# PDM_2021.net
KiCad netlist of a schematic drawn in EAGLE
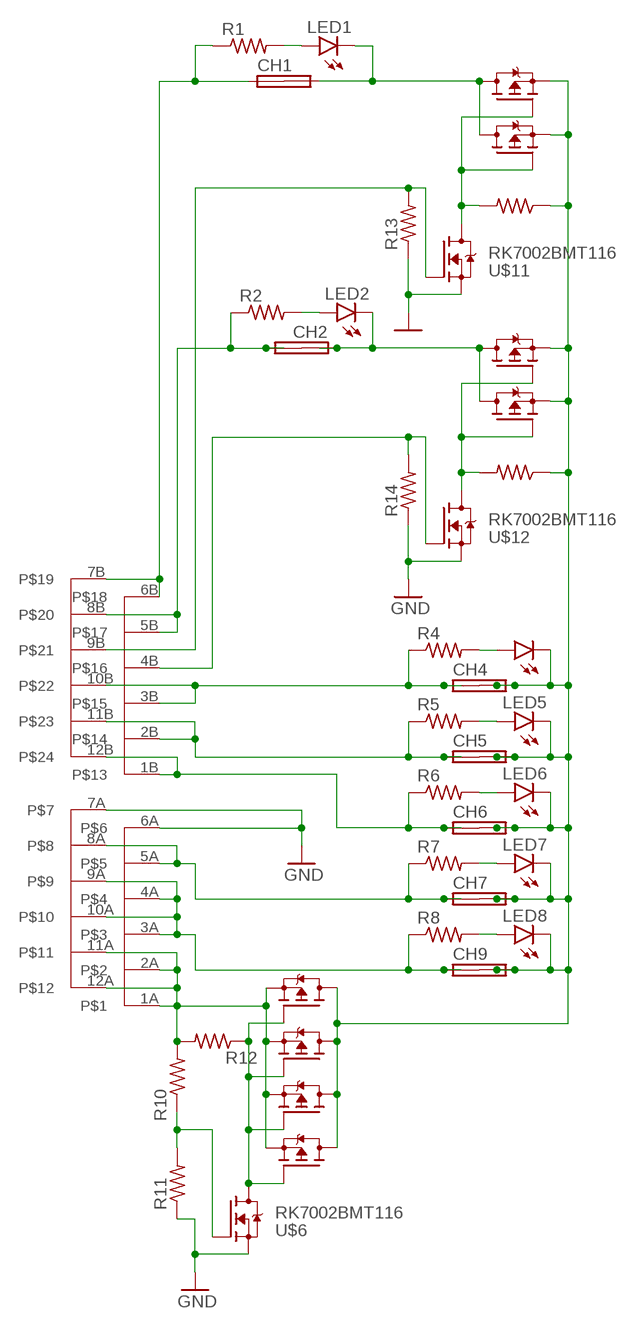
[diagram p0: schematic, sheet 1]

(export (version "E")
  (design (tool "Eeschema 10.0.6"))
  (components
    (comp (ref "CH1")
      (value "3568FUSEHOLDER")
      (footprint "eagle-import:3568")
      (libsource (lib "eagle-import") (part "3568FUSEHOLDER"))
    )
    (comp (ref "CH2")
      (value "3568FUSEHOLDER")
      (footprint "eagle-import:3568")
      (libsource (lib "eagle-import") (part "3568FUSEHOLDER"))
    )
    (comp (ref "CH4")
      (value "3568FUSEHOLDER")
      (footprint "eagle-import:3568")
      (libsource (lib "eagle-import") (part "3568FUSEHOLDER"))
    )
    (comp (ref "CH5")
      (value "3568FUSEHOLDER")
      (footprint "eagle-import:3568")
      (libsource (lib "eagle-import") (part "3568FUSEHOLDER"))
    )
    (comp (ref "CH6")
      (value "3568FUSEHOLDER")
      (footprint "eagle-import:3568")
      (libsource (lib "eagle-import") (part "3568FUSEHOLDER"))
    )
    (comp (ref "CH7")
      (value "3568FUSEHOLDER")
      (footprint "eagle-import:3568")
      (libsource (lib "eagle-import") (part "3568FUSEHOLDER"))
    )
    (comp (ref "CH9")
      (value "3568FUSEHOLDER")
      (footprint "eagle-import:3568")
      (libsource (lib "eagle-import") (part "3568FUSEHOLDER"))
    )
    (comp (ref "LED1")
      (value "LEDCHIP-LED0805")
      (footprint "eagle-import:CHIP-LED0805")
      (libsource (lib "eagle-import") (part "LEDCHIP-LED0805"))
    )
    (comp (ref "LED2")
      (value "LEDCHIP-LED0805")
      (footprint "eagle-import:CHIP-LED0805")
      (libsource (lib "eagle-import") (part "LEDCHIP-LED0805"))
    )
    (comp (ref "LED4")
      (value "LEDCHIP-LED0805")
      (footprint "eagle-import:CHIP-LED0805")
      (libsource (lib "eagle-import") (part "LEDCHIP-LED0805"))
    )
    (comp (ref "LED5")
      (value "LEDCHIP-LED0805")
      (footprint "eagle-import:CHIP-LED0805")
      (libsource (lib "eagle-import") (part "LEDCHIP-LED0805"))
    )
    (comp (ref "LED6")
      (value "LEDCHIP-LED0805")
      (footprint "eagle-import:CHIP-LED0805")
      (libsource (lib "eagle-import") (part "LEDCHIP-LED0805"))
    )
    (comp (ref "LED7")
      (value "LEDCHIP-LED0805")
      (footprint "eagle-import:CHIP-LED0805")
      (libsource (lib "eagle-import") (part "LEDCHIP-LED0805"))
    )
    (comp (ref "LED8")
      (value "LEDCHIP-LED0805")
      (footprint "eagle-import:CHIP-LED0805")
      (libsource (lib "eagle-import") (part "LEDCHIP-LED0805"))
    )
    (comp (ref "R1")
      (value "R-US_R0805")
      (footprint "eagle-import:R0805")
      (libsource (lib "eagle-import") (part "R-US_R0805"))
    )
    (comp (ref "R2")
      (value "R-US_R0805")
      (footprint "eagle-import:R0805")
      (libsource (lib "eagle-import") (part "R-US_R0805"))
    )
    (comp (ref "R4")
      (value "R-US_R0805")
      (footprint "eagle-import:R0805")
      (libsource (lib "eagle-import") (part "R-US_R0805"))
    )
    (comp (ref "R5")
      (value "R-US_R0805")
      (footprint "eagle-import:R0805")
      (libsource (lib "eagle-import") (part "R-US_R0805"))
    )
    (comp (ref "R6")
      (value "R-US_R0805")
      (footprint "eagle-import:R0805")
      (libsource (lib "eagle-import") (part "R-US_R0805"))
    )
    (comp (ref "R7")
      (value "R-US_R0805")
      (footprint "eagle-import:R0805")
      (libsource (lib "eagle-import") (part "R-US_R0805"))
    )
    (comp (ref "R8")
      (value "R-US_R0805")
      (footprint "eagle-import:R0805")
      (libsource (lib "eagle-import") (part "R-US_R0805"))
    )
    (comp (ref "R10")
      (value "R-US_R0805")
      (footprint "eagle-import:R0805")
      (libsource (lib "eagle-import") (part "R-US_R0805"))
    )
    (comp (ref "R11")
      (value "R-US_R0805")
      (footprint "eagle-import:R0805")
      (libsource (lib "eagle-import") (part "R-US_R0805"))
    )
    (comp (ref "R12")
      (value "R-US_R0805")
      (footprint "eagle-import:R0805")
      (libsource (lib "eagle-import") (part "R-US_R0805"))
    )
    (comp (ref "R13")
      (value "R-US_R0805")
      (footprint "eagle-import:R0805")
      (libsource (lib "eagle-import") (part "R-US_R0805"))
    )
    (comp (ref "R14")
      (value "R-US_R0805")
      (footprint "eagle-import:R0805")
      (libsource (lib "eagle-import") (part "R-US_R0805"))
    )
    (comp (ref "R15")
      (value "R-US_R0805")
      (footprint "eagle-import:R0805")
      (libsource (lib "eagle-import") (part "R-US_R0805"))
    )
    (comp (ref "R16")
      (value "R-US_R0805")
      (footprint "eagle-import:R0805")
      (libsource (lib "eagle-import") (part "R-US_R0805"))
    )
    (comp (ref "U$1")
      (value "_CUSTOM_111_CUSTOM_SQJ407EP-T1_GE3")
      (footprint "eagle-import:_CUSTOM_111_CUSTOM_TRANS_SIRA90DP-T1-GE3")
      (libsource (lib "eagle-import") (part "_CUSTOM_111_CUSTOM_SQJ407EP-T1_GE3"))
    )
    (comp (ref "U$2")
      (value "_CUSTOM_111_CUSTOM_SQJ407EP-T1_GE3")
      (footprint "eagle-import:_CUSTOM_111_CUSTOM_TRANS_SIRA90DP-T1-GE3")
      (libsource (lib "eagle-import") (part "_CUSTOM_111_CUSTOM_SQJ407EP-T1_GE3"))
    )
    (comp (ref "U$3")
      (value "_CUSTOM_111_CUSTOM_SQJ407EP-T1_GE3")
      (footprint "eagle-import:_CUSTOM_111_CUSTOM_TRANS_SIRA90DP-T1-GE3")
      (libsource (lib "eagle-import") (part "_CUSTOM_111_CUSTOM_SQJ407EP-T1_GE3"))
    )
    (comp (ref "U$4")
      (value "DTM1312PA12BR008")
      (footprint "eagle-import:DE_12X2_PIN_HEADER")
      (libsource (lib "eagle-import") (part "DTM1312PA12BR008"))
    )
    (comp (ref "U$5")
      (value "_CUSTOM_111_CUSTOM_SQJ407EP-T1_GE3")
      (footprint "eagle-import:_CUSTOM_111_CUSTOM_TRANS_SIRA90DP-T1-GE3")
      (libsource (lib "eagle-import") (part "_CUSTOM_111_CUSTOM_SQJ407EP-T1_GE3"))
    )
    (comp (ref "U$6")
      (value "RK7002BMT116")
      (footprint "eagle-import:SOT23")
      (libsource (lib "eagle-import") (part "RK7002BMT116"))
    )
    (comp (ref "U$7")
      (value "_CUSTOM_111_CUSTOM_SQJ407EP-T1_GE3")
      (footprint "eagle-import:_CUSTOM_111_CUSTOM_TRANS_SIRA90DP-T1-GE3")
      (libsource (lib "eagle-import") (part "_CUSTOM_111_CUSTOM_SQJ407EP-T1_GE3"))
    )
    (comp (ref "U$8")
      (value "_CUSTOM_111_CUSTOM_SQJ407EP-T1_GE3")
      (footprint "eagle-import:_CUSTOM_111_CUSTOM_TRANS_SIRA90DP-T1-GE3")
      (libsource (lib "eagle-import") (part "_CUSTOM_111_CUSTOM_SQJ407EP-T1_GE3"))
    )
    (comp (ref "U$9")
      (value "_CUSTOM_111_CUSTOM_SQJ407EP-T1_GE3")
      (footprint "eagle-import:_CUSTOM_111_CUSTOM_TRANS_SIRA90DP-T1-GE3")
      (libsource (lib "eagle-import") (part "_CUSTOM_111_CUSTOM_SQJ407EP-T1_GE3"))
    )
    (comp (ref "U$10")
      (value "_CUSTOM_111_CUSTOM_SQJ407EP-T1_GE3")
      (footprint "eagle-import:_CUSTOM_111_CUSTOM_TRANS_SIRA90DP-T1-GE3")
      (libsource (lib "eagle-import") (part "_CUSTOM_111_CUSTOM_SQJ407EP-T1_GE3"))
    )
    (comp (ref "U$11")
      (value "RK7002BMT116")
      (footprint "eagle-import:SOT23")
      (libsource (lib "eagle-import") (part "RK7002BMT116"))
    )
    (comp (ref "U$12")
      (value "RK7002BMT116")
      (footprint "eagle-import:SOT23")
      (libsource (lib "eagle-import") (part "RK7002BMT116"))
    )
  )
  (nets
    (net (code "1") (name "GND") (class "Default")
      (node (ref "R11") (pin "1") (pinfunction "1_1") (pintype "passive"))
      (node (ref "R13") (pin "1") (pinfunction "1_1") (pintype "passive"))
      (node (ref "R14") (pin "1") (pinfunction "1_1") (pintype "passive"))
      (node (ref "U$11") (pin "2") (pinfunction "S_2") (pintype "passive"))
      (node (ref "U$12") (pin "2") (pinfunction "S_2") (pintype "passive"))
      (node (ref "U$4") (pin "6A") (pinfunction "P$6_6A") (pintype "bidirectional"))
      (node (ref "U$4") (pin "7A") (pinfunction "P$7_7A") (pintype "bidirectional"))
      (node (ref "U$6") (pin "2") (pinfunction "S_2") (pintype "passive"))
    )
    (net (code "2") (name "Net-(CH1-1A)") (class "Default")
      (node (ref "CH1") (pin "L1") (pinfunction "1A_L1") (pintype "passive"))
      (node (ref "R1") (pin "1") (pinfunction "1_1") (pintype "passive"))
      (node (ref "U$4") (pin "6B") (pinfunction "P$18_6B") (pintype "bidirectional"))
      (node (ref "U$4") (pin "7B") (pinfunction "P$19_7B") (pintype "bidirectional"))
    )
    (net (code "3") (name "Net-(CH1-2A)") (class "Default")
      (node (ref "CH1") (pin "R1") (pinfunction "2A_R1") (pintype "passive"))
      (node (ref "LED1") (pin "C") (pinfunction "C_C") (pintype "passive"))
      (node (ref "U$7") (pin "5") (pinfunction "D_5") (pintype "passive"))
      (node (ref "U$8") (pin "5") (pinfunction "D_5") (pintype "passive"))
    )
    (net (code "4") (name "Net-(CH2-1A)") (class "Default")
      (node (ref "CH2") (pin "L1") (pinfunction "1A_L1") (pintype "passive"))
      (node (ref "CH2") (pin "L2") (pinfunction "1B_L2") (pintype "passive"))
      (node (ref "R2") (pin "1") (pinfunction "1_1") (pintype "passive"))
      (node (ref "U$4") (pin "5B") (pinfunction "P$17_5B") (pintype "bidirectional"))
      (node (ref "U$4") (pin "8B") (pinfunction "P$20_8B") (pintype "bidirectional"))
    )
    (net (code "5") (name "Net-(CH2-2A)") (class "Default")
      (node (ref "CH2") (pin "R1") (pinfunction "2A_R1") (pintype "passive"))
      (node (ref "CH2") (pin "R2") (pinfunction "2B_R2") (pintype "passive"))
      (node (ref "LED2") (pin "C") (pinfunction "C_C") (pintype "passive"))
      (node (ref "U$10") (pin "5") (pinfunction "D_5") (pintype "passive"))
      (node (ref "U$9") (pin "5") (pinfunction "D_5") (pintype "passive"))
    )
    (net (code "6") (name "Net-(CH4-1A)") (class "Default")
      (node (ref "CH4") (pin "L1") (pinfunction "1A_L1") (pintype "passive"))
      (node (ref "CH4") (pin "L2") (pinfunction "1B_L2") (pintype "passive"))
      (node (ref "R4") (pin "1") (pinfunction "1_1") (pintype "passive"))
      (node (ref "U$4") (pin "10B") (pinfunction "P$22_10B") (pintype "bidirectional"))
      (node (ref "U$4") (pin "3B") (pinfunction "P$15_3B") (pintype "bidirectional"))
    )
    (net (code "7") (name "Net-(CH4-2A)") (class "Default")
      (node (ref "CH4") (pin "R1") (pinfunction "2A_R1") (pintype "passive"))
      (node (ref "CH4") (pin "R2") (pinfunction "2B_R2") (pintype "passive"))
      (node (ref "CH5") (pin "R1") (pinfunction "2A_R1") (pintype "passive"))
      (node (ref "CH5") (pin "R2") (pinfunction "2B_R2") (pintype "passive"))
      (node (ref "CH6") (pin "R1") (pinfunction "2A_R1") (pintype "passive"))
      (node (ref "CH6") (pin "R2") (pinfunction "2B_R2") (pintype "passive"))
      (node (ref "CH7") (pin "R1") (pinfunction "2A_R1") (pintype "passive"))
      (node (ref "CH7") (pin "R2") (pinfunction "2B_R2") (pintype "passive"))
      (node (ref "CH9") (pin "R1") (pinfunction "2A_R1") (pintype "passive"))
      (node (ref "CH9") (pin "R2") (pinfunction "2B_R2") (pintype "passive"))
      (node (ref "LED4") (pin "C") (pinfunction "C_C") (pintype "passive"))
      (node (ref "LED5") (pin "C") (pinfunction "C_C") (pintype "passive"))
      (node (ref "LED6") (pin "C") (pinfunction "C_C") (pintype "passive"))
      (node (ref "LED7") (pin "C") (pinfunction "C_C") (pintype "passive"))
      (node (ref "LED8") (pin "C") (pinfunction "C_C") (pintype "passive"))
      (node (ref "R15") (pin "1") (pinfunction "1_1") (pintype "passive"))
      (node (ref "R16") (pin "1") (pinfunction "1_1") (pintype "passive"))
      (node (ref "U$1") (pin "5") (pinfunction "D_5") (pintype "passive"))
      (node (ref "U$10") (pin "1") (pinfunction "S_1") (pintype "passive"))
      (node (ref "U$10") (pin "2") (pinfunction "S_2") (pintype "passive"))
      (node (ref "U$10") (pin "3") (pinfunction "S_3") (pintype "passive"))
      (node (ref "U$2") (pin "5") (pinfunction "D_5") (pintype "passive"))
      (node (ref "U$3") (pin "5") (pinfunction "D_5") (pintype "passive"))
      (node (ref "U$5") (pin "5") (pinfunction "D_5") (pintype "passive"))
      (node (ref "U$7") (pin "1") (pinfunction "S_1") (pintype "passive"))
      (node (ref "U$7") (pin "2") (pinfunction "S_2") (pintype "passive"))
      (node (ref "U$7") (pin "3") (pinfunction "S_3") (pintype "passive"))
      (node (ref "U$8") (pin "1") (pinfunction "S_1") (pintype "passive"))
      (node (ref "U$8") (pin "2") (pinfunction "S_2") (pintype "passive"))
      (node (ref "U$8") (pin "3") (pinfunction "S_3") (pintype "passive"))
      (node (ref "U$9") (pin "1") (pinfunction "S_1") (pintype "passive"))
      (node (ref "U$9") (pin "2") (pinfunction "S_2") (pintype "passive"))
      (node (ref "U$9") (pin "3") (pinfunction "S_3") (pintype "passive"))
    )
    (net (code "8") (name "Net-(CH5-1A)") (class "Default")
      (node (ref "CH5") (pin "L1") (pinfunction "1A_L1") (pintype "passive"))
      (node (ref "CH5") (pin "L2") (pinfunction "1B_L2") (pintype "passive"))
      (node (ref "R5") (pin "1") (pinfunction "1_1") (pintype "passive"))
      (node (ref "U$4") (pin "11B") (pinfunction "P$23_11B") (pintype "bidirectional"))
      (node (ref "U$4") (pin "2B") (pinfunction "P$14_2B") (pintype "bidirectional"))
    )
    (net (code "9") (name "Net-(CH6-1A)") (class "Default")
      (node (ref "CH6") (pin "L1") (pinfunction "1A_L1") (pintype "passive"))
      (node (ref "CH6") (pin "L2") (pinfunction "1B_L2") (pintype "passive"))
      (node (ref "R6") (pin "1") (pinfunction "1_1") (pintype "passive"))
      (node (ref "U$4") (pin "12B") (pinfunction "P$24_12B") (pintype "bidirectional"))
      (node (ref "U$4") (pin "1B") (pinfunction "P$13_1B") (pintype "bidirectional"))
    )
    (net (code "10") (name "Net-(CH7-1A)") (class "Default")
      (node (ref "CH7") (pin "L1") (pinfunction "1A_L1") (pintype "passive"))
      (node (ref "CH7") (pin "L2") (pinfunction "1B_L2") (pintype "passive"))
      (node (ref "R7") (pin "1") (pinfunction "1_1") (pintype "passive"))
      (node (ref "U$4") (pin "5A") (pinfunction "P$5_5A") (pintype "bidirectional"))
      (node (ref "U$4") (pin "8A") (pinfunction "P$8_8A") (pintype "bidirectional"))
    )
    (net (code "11") (name "Net-(CH9-1A)") (class "Default")
      (node (ref "CH9") (pin "L1") (pinfunction "1A_L1") (pintype "passive"))
      (node (ref "CH9") (pin "L2") (pinfunction "1B_L2") (pintype "passive"))
      (node (ref "R8") (pin "1") (pinfunction "1_1") (pintype "passive"))
      (node (ref "U$4") (pin "10A") (pinfunction "P$10_10A") (pintype "bidirectional"))
      (node (ref "U$4") (pin "3A") (pinfunction "P$3_3A") (pintype "bidirectional"))
      (node (ref "U$4") (pin "4A") (pinfunction "P$4_4A") (pintype "bidirectional"))
      (node (ref "U$4") (pin "9A") (pinfunction "P$9_9A") (pintype "bidirectional"))
    )
    (net (code "12") (name "Net-(LED1-PadA)") (class "Default")
      (node (ref "LED1") (pin "A") (pinfunction "A_A") (pintype "passive"))
      (node (ref "R1") (pin "2") (pinfunction "2_2") (pintype "passive"))
    )
    (net (code "13") (name "Net-(LED2-PadA)") (class "Default")
      (node (ref "LED2") (pin "A") (pinfunction "A_A") (pintype "passive"))
      (node (ref "R2") (pin "2") (pinfunction "2_2") (pintype "passive"))
    )
    (net (code "14") (name "Net-(LED4-PadA)") (class "Default")
      (node (ref "LED4") (pin "A") (pinfunction "A_A") (pintype "passive"))
      (node (ref "R4") (pin "2") (pinfunction "2_2") (pintype "passive"))
    )
    (net (code "15") (name "Net-(LED5-PadA)") (class "Default")
      (node (ref "LED5") (pin "A") (pinfunction "A_A") (pintype "passive"))
      (node (ref "R5") (pin "2") (pinfunction "2_2") (pintype "passive"))
    )
    (net (code "16") (name "Net-(LED6-PadA)") (class "Default")
      (node (ref "LED6") (pin "A") (pinfunction "A_A") (pintype "passive"))
      (node (ref "R6") (pin "2") (pinfunction "2_2") (pintype "passive"))
    )
    (net (code "17") (name "Net-(LED7-PadA)") (class "Default")
      (node (ref "LED7") (pin "A") (pinfunction "A_A") (pintype "passive"))
      (node (ref "R7") (pin "2") (pinfunction "2_2") (pintype "passive"))
    )
    (net (code "18") (name "Net-(LED8-PadA)") (class "Default")
      (node (ref "LED8") (pin "A") (pinfunction "A_A") (pintype "passive"))
      (node (ref "R8") (pin "2") (pinfunction "2_2") (pintype "passive"))
    )
    (net (code "19") (name "Net-(U$1-G)") (class "Default")
      (node (ref "R12") (pin "1") (pinfunction "1_1") (pintype "passive"))
      (node (ref "U$1") (pin "4") (pinfunction "G_4") (pintype "passive"))
      (node (ref "U$2") (pin "4") (pinfunction "G_4") (pintype "passive"))
      (node (ref "U$3") (pin "4") (pinfunction "G_4") (pintype "passive"))
      (node (ref "U$5") (pin "4") (pinfunction "G_4") (pintype "passive"))
      (node (ref "U$6") (pin "3") (pinfunction "D_3") (pintype "passive"))
    )
    (net (code "20") (name "Net-(U$4-P$1)") (class "Default")
      (node (ref "R10") (pin "2") (pinfunction "2_2") (pintype "passive"))
      (node (ref "R12") (pin "2") (pinfunction "2_2") (pintype "passive"))
      (node (ref "U$1") (pin "1") (pinfunction "S_1") (pintype "passive"))
      (node (ref "U$1") (pin "2") (pinfunction "S_2") (pintype "passive"))
      (node (ref "U$1") (pin "3") (pinfunction "S_3") (pintype "passive"))
      (node (ref "U$2") (pin "1") (pinfunction "S_1") (pintype "passive"))
      (node (ref "U$2") (pin "2") (pinfunction "S_2") (pintype "passive"))
      (node (ref "U$2") (pin "3") (pinfunction "S_3") (pintype "passive"))
      (node (ref "U$3") (pin "1") (pinfunction "S_1") (pintype "passive"))
      (node (ref "U$3") (pin "2") (pinfunction "S_2") (pintype "passive"))
      (node (ref "U$3") (pin "3") (pinfunction "S_3") (pintype "passive"))
      (node (ref "U$4") (pin "11A") (pinfunction "P$11_11A") (pintype "bidirectional"))
      (node (ref "U$4") (pin "12A") (pinfunction "P$12_12A") (pintype "bidirectional"))
      (node (ref "U$4") (pin "1A") (pinfunction "P$1_1A") (pintype "bidirectional"))
      (node (ref "U$4") (pin "2A") (pinfunction "P$2_2A") (pintype "bidirectional"))
      (node (ref "U$5") (pin "1") (pinfunction "S_1") (pintype "passive"))
      (node (ref "U$5") (pin "2") (pinfunction "S_2") (pintype "passive"))
      (node (ref "U$5") (pin "3") (pinfunction "S_3") (pintype "passive"))
    )
    (net (code "21") (name "Net-(U$6-G)") (class "Default")
      (node (ref "R10") (pin "1") (pinfunction "1_1") (pintype "passive"))
      (node (ref "R11") (pin "2") (pinfunction "2_2") (pintype "passive"))
      (node (ref "U$6") (pin "1") (pinfunction "G_1") (pintype "passive"))
    )
    (net (code "22") (name "Net-(U$10-G)") (class "Default")
      (node (ref "R15") (pin "2") (pinfunction "2_2") (pintype "passive"))
      (node (ref "U$10") (pin "4") (pinfunction "G_4") (pintype "passive"))
      (node (ref "U$12") (pin "3") (pinfunction "D_3") (pintype "passive"))
      (node (ref "U$9") (pin "4") (pinfunction "G_4") (pintype "passive"))
    )
    (net (code "23") (name "Net-(U$11-D)") (class "Default")
      (node (ref "R16") (pin "2") (pinfunction "2_2") (pintype "passive"))
      (node (ref "U$11") (pin "3") (pinfunction "D_3") (pintype "passive"))
      (node (ref "U$7") (pin "4") (pinfunction "G_4") (pintype "passive"))
      (node (ref "U$8") (pin "4") (pinfunction "G_4") (pintype "passive"))
    )
    (net (code "24") (name "Net-(U$11-G)") (class "Default")
      (node (ref "R13") (pin "2") (pinfunction "2_2") (pintype "passive"))
      (node (ref "U$11") (pin "1") (pinfunction "G_1") (pintype "passive"))
      (node (ref "U$4") (pin "9B") (pinfunction "P$21_9B") (pintype "bidirectional"))
    )
    (net (code "25") (name "Net-(U$12-G)") (class "Default")
      (node (ref "R14") (pin "2") (pinfunction "2_2") (pintype "passive"))
      (node (ref "U$12") (pin "1") (pinfunction "G_1") (pintype "passive"))
      (node (ref "U$4") (pin "4B") (pinfunction "P$16_4B") (pintype "bidirectional"))
    )
    (net (code "26") (name "unconnected-(CH1-1B-PadL2)") (class "Default")
      (node (ref "CH1") (pin "L2") (pinfunction "1B_L2") (pintype "passive"))
    )
    (net (code "27") (name "unconnected-(CH1-2B-PadR2)") (class "Default")
      (node (ref "CH1") (pin "R2") (pinfunction "2B_R2") (pintype "passive"))
    )
  )
)
